# schematic.net
KiCad netlist of a schematic drawn in EAGLE
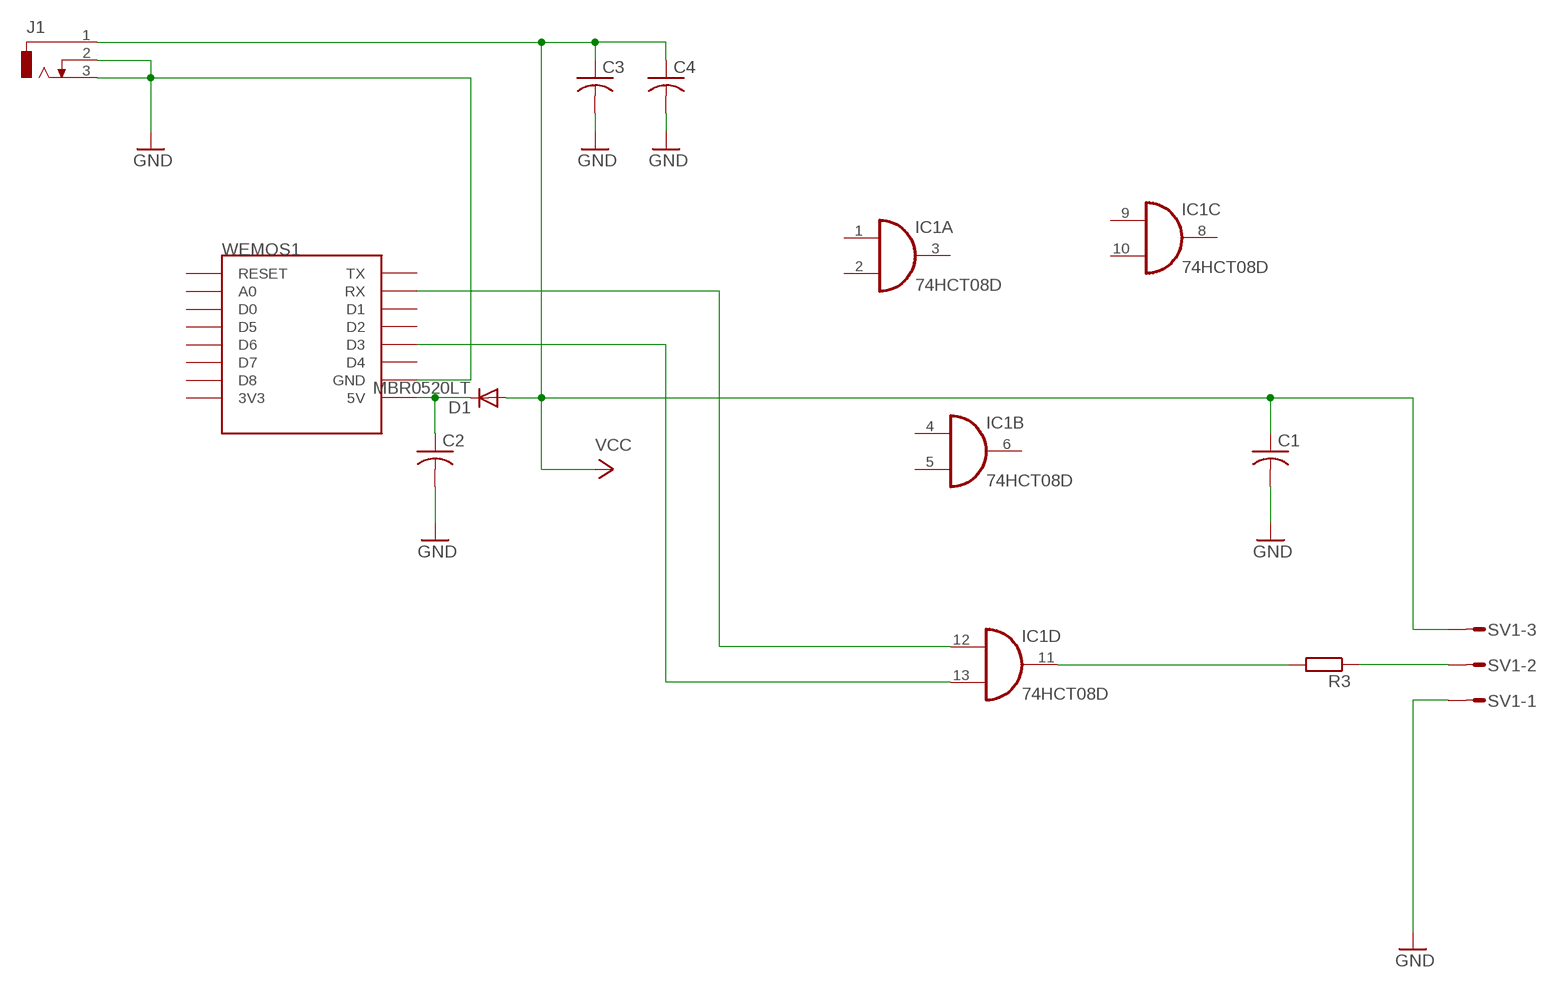
[diagram p0: schematic, sheet 1]

(export (version "E")
  (design (tool "Eeschema 10.0.6"))
  (components
    (comp (ref "C1")
      (value "C-USC1206")
      (footprint "eagle-import:C1206")
      (libsource (lib "eagle-import") (part "C-USC1206"))
    )
    (comp (ref "C2")
      (value "C-USC1206")
      (footprint "eagle-import:C1206")
      (libsource (lib "eagle-import") (part "C-USC1206"))
    )
    (comp (ref "C3")
      (value "C-USC1206")
      (footprint "eagle-import:C1206")
      (libsource (lib "eagle-import") (part "C-USC1206"))
    )
    (comp (ref "C4")
      (value "C-USC1206")
      (footprint "eagle-import:C1206")
      (libsource (lib "eagle-import") (part "C-USC1206"))
    )
    (comp (ref "D1")
      (value "MBR0520LT")
      (footprint "eagle-import:SOD123")
      (libsource (lib "eagle-import") (part "MBR0520LT"))
    )
    (comp (ref "IC1")
      (value "74HCT08D")
      (footprint "eagle-import:SO14")
      (libsource (lib "eagle-import") (part "7408DHCT"))
    )
    (comp (ref "J1")
      (value "DCJ0303")
      (footprint "eagle-import:DCJ0303")
      (libsource (lib "eagle-import") (part "DCJ0303"))
    )
    (comp (ref "R3")
      (value "R-EU_M1206")
      (footprint "eagle-import:M1206")
      (libsource (lib "eagle-import") (part "R-EU_M1206"))
    )
    (comp (ref "SV1")
      (value "S03P")
      (footprint "eagle-import:S03P")
      (libsource (lib "eagle-import") (part "S03P"))
    )
    (comp (ref "WEMOS1")
      (value "WEMOS-D1-MINI")
      (footprint "eagle-import:WEMOS-D1-MINI")
      (libsource (lib "eagle-import") (part "WEMOS-D1-MINI"))
    )
  )
  (nets
    (net (code "1") (name "GND") (class "Default")
      (node (ref "C1") (pin "2") (pinfunction "2_2") (pintype "passive"))
      (node (ref "C2") (pin "2") (pinfunction "2_2") (pintype "passive"))
      (node (ref "C3") (pin "2") (pinfunction "2_2") (pintype "passive"))
      (node (ref "C4") (pin "2") (pinfunction "2_2") (pintype "passive"))
      (node (ref "J1") (pin "2") (pinfunction "2_2") (pintype "passive"))
      (node (ref "J1") (pin "3") (pinfunction "3_3") (pintype "passive"))
      (node (ref "SV1") (pin "1") (pinfunction "S_1") (pintype "passive"))
      (node (ref "WEMOS1") (pin "GND") (pinfunction "GND_GND") (pintype "bidirectional"))
    )
    (net (code "2") (name "Net-(C2-Pad1)") (class "Default")
      (node (ref "C2") (pin "1") (pinfunction "1_1") (pintype "passive"))
      (node (ref "D1") (pin "C") (pinfunction "C_C") (pintype "passive"))
      (node (ref "WEMOS1") (pin "5V") (pinfunction "5V_5V") (pintype "bidirectional"))
    )
    (net (code "3") (name "Net-(IC1D-I0)") (class "Default")
      (node (ref "IC1") (pin "12") (pinfunction "I0_12") (pintype "input"))
      (node (ref "WEMOS1") (pin "RX") (pinfunction "RX_RX") (pintype "bidirectional"))
    )
    (net (code "4") (name "Net-(IC1D-I1)") (class "Default")
      (node (ref "IC1") (pin "13") (pinfunction "I1_13") (pintype "input"))
      (node (ref "WEMOS1") (pin "D3") (pinfunction "D3_D3") (pintype "bidirectional"))
    )
    (net (code "5") (name "Net-(IC1D-O)") (class "Default")
      (node (ref "IC1") (pin "11") (pinfunction "O_11") (pintype "output"))
      (node (ref "R3") (pin "2") (pinfunction "2_2") (pintype "passive"))
    )
    (net (code "6") (name "Net-(SV1B-S)") (class "Default")
      (node (ref "R3") (pin "1") (pinfunction "1_1") (pintype "passive"))
      (node (ref "SV1") (pin "2") (pinfunction "S_2") (pintype "passive"))
    )
    (net (code "7") (name "VCC") (class "Default")
      (node (ref "C1") (pin "1") (pinfunction "1_1") (pintype "passive"))
      (node (ref "C3") (pin "1") (pinfunction "1_1") (pintype "passive"))
      (node (ref "C4") (pin "1") (pinfunction "1_1") (pintype "passive"))
      (node (ref "D1") (pin "A") (pinfunction "A_A") (pintype "passive"))
      (node (ref "J1") (pin "1") (pinfunction "1_1") (pintype "passive"))
      (node (ref "SV1") (pin "3") (pinfunction "S_3") (pintype "passive"))
    )
    (net (code "8") (name "unconnected-(IC1A-I0-Pad1)") (class "Default")
      (node (ref "IC1") (pin "1") (pinfunction "I0_1") (pintype "input"))
    )
    (net (code "9") (name "unconnected-(IC1A-I1-Pad2)") (class "Default")
      (node (ref "IC1") (pin "2") (pinfunction "I1_2") (pintype "input"))
    )
    (net (code "10") (name "unconnected-(IC1A-O-Pad3)") (class "Default")
      (node (ref "IC1") (pin "3") (pinfunction "O_3") (pintype "output"))
    )
    (net (code "11") (name "unconnected-(IC1B-I0-Pad4)") (class "Default")
      (node (ref "IC1") (pin "4") (pinfunction "I0_4") (pintype "input"))
    )
    (net (code "12") (name "unconnected-(IC1B-I1-Pad5)") (class "Default")
      (node (ref "IC1") (pin "5") (pinfunction "I1_5") (pintype "input"))
    )
    (net (code "13") (name "unconnected-(IC1B-O-Pad6)") (class "Default")
      (node (ref "IC1") (pin "6") (pinfunction "O_6") (pintype "output"))
    )
    (net (code "14") (name "unconnected-(IC1C-I0-Pad9)") (class "Default")
      (node (ref "IC1") (pin "9") (pinfunction "I0_9") (pintype "input"))
    )
    (net (code "15") (name "unconnected-(IC1C-I1-Pad10)") (class "Default")
      (node (ref "IC1") (pin "10") (pinfunction "I1_10") (pintype "input"))
    )
    (net (code "16") (name "unconnected-(IC1C-O-Pad8)") (class "Default")
      (node (ref "IC1") (pin "8") (pinfunction "O_8") (pintype "output"))
    )
    (net (code "17") (name "unconnected-(WEMOS1-Pad3V3)") (class "Default")
      (node (ref "WEMOS1") (pin "3V3") (pinfunction "3V3_3V3") (pintype "bidirectional"))
    )
    (net (code "18") (name "unconnected-(WEMOS1-PadA0)") (class "Default")
      (node (ref "WEMOS1") (pin "A0") (pinfunction "A0_A0") (pintype "bidirectional"))
    )
    (net (code "19") (name "unconnected-(WEMOS1-PadD0)") (class "Default")
      (node (ref "WEMOS1") (pin "D0") (pinfunction "D0_D0") (pintype "bidirectional"))
    )
    (net (code "20") (name "unconnected-(WEMOS1-PadD1)") (class "Default")
      (node (ref "WEMOS1") (pin "D1") (pinfunction "D1_D1") (pintype "bidirectional"))
    )
    (net (code "21") (name "unconnected-(WEMOS1-PadD2)") (class "Default")
      (node (ref "WEMOS1") (pin "D2") (pinfunction "D2_D2") (pintype "bidirectional"))
    )
    (net (code "22") (name "unconnected-(WEMOS1-PadD4)") (class "Default")
      (node (ref "WEMOS1") (pin "D4") (pinfunction "D4_D4") (pintype "bidirectional"))
    )
    (net (code "23") (name "unconnected-(WEMOS1-PadD5)") (class "Default")
      (node (ref "WEMOS1") (pin "D5") (pinfunction "D5_D5") (pintype "bidirectional"))
    )
    (net (code "24") (name "unconnected-(WEMOS1-PadD6)") (class "Default")
      (node (ref "WEMOS1") (pin "D6") (pinfunction "D6_D6") (pintype "bidirectional"))
    )
    (net (code "25") (name "unconnected-(WEMOS1-PadD7)") (class "Default")
      (node (ref "WEMOS1") (pin "D7") (pinfunction "D7_D7") (pintype "bidirectional"))
    )
    (net (code "26") (name "unconnected-(WEMOS1-PadD8)") (class "Default")
      (node (ref "WEMOS1") (pin "D8") (pinfunction "D8_D8") (pintype "bidirectional"))
    )
    (net (code "27") (name "unconnected-(WEMOS1-PadRESET)") (class "Default")
      (node (ref "WEMOS1") (pin "RESET") (pinfunction "RESET_RESET") (pintype "bidirectional"))
    )
    (net (code "28") (name "unconnected-(WEMOS1-PadTX)") (class "Default")
      (node (ref "WEMOS1") (pin "TX") (pinfunction "TX_TX") (pintype "bidirectional"))
    )
  )
)
